# STM32F1_Rev0_2.net
KiCad netlist of a schematic drawn in EAGLE
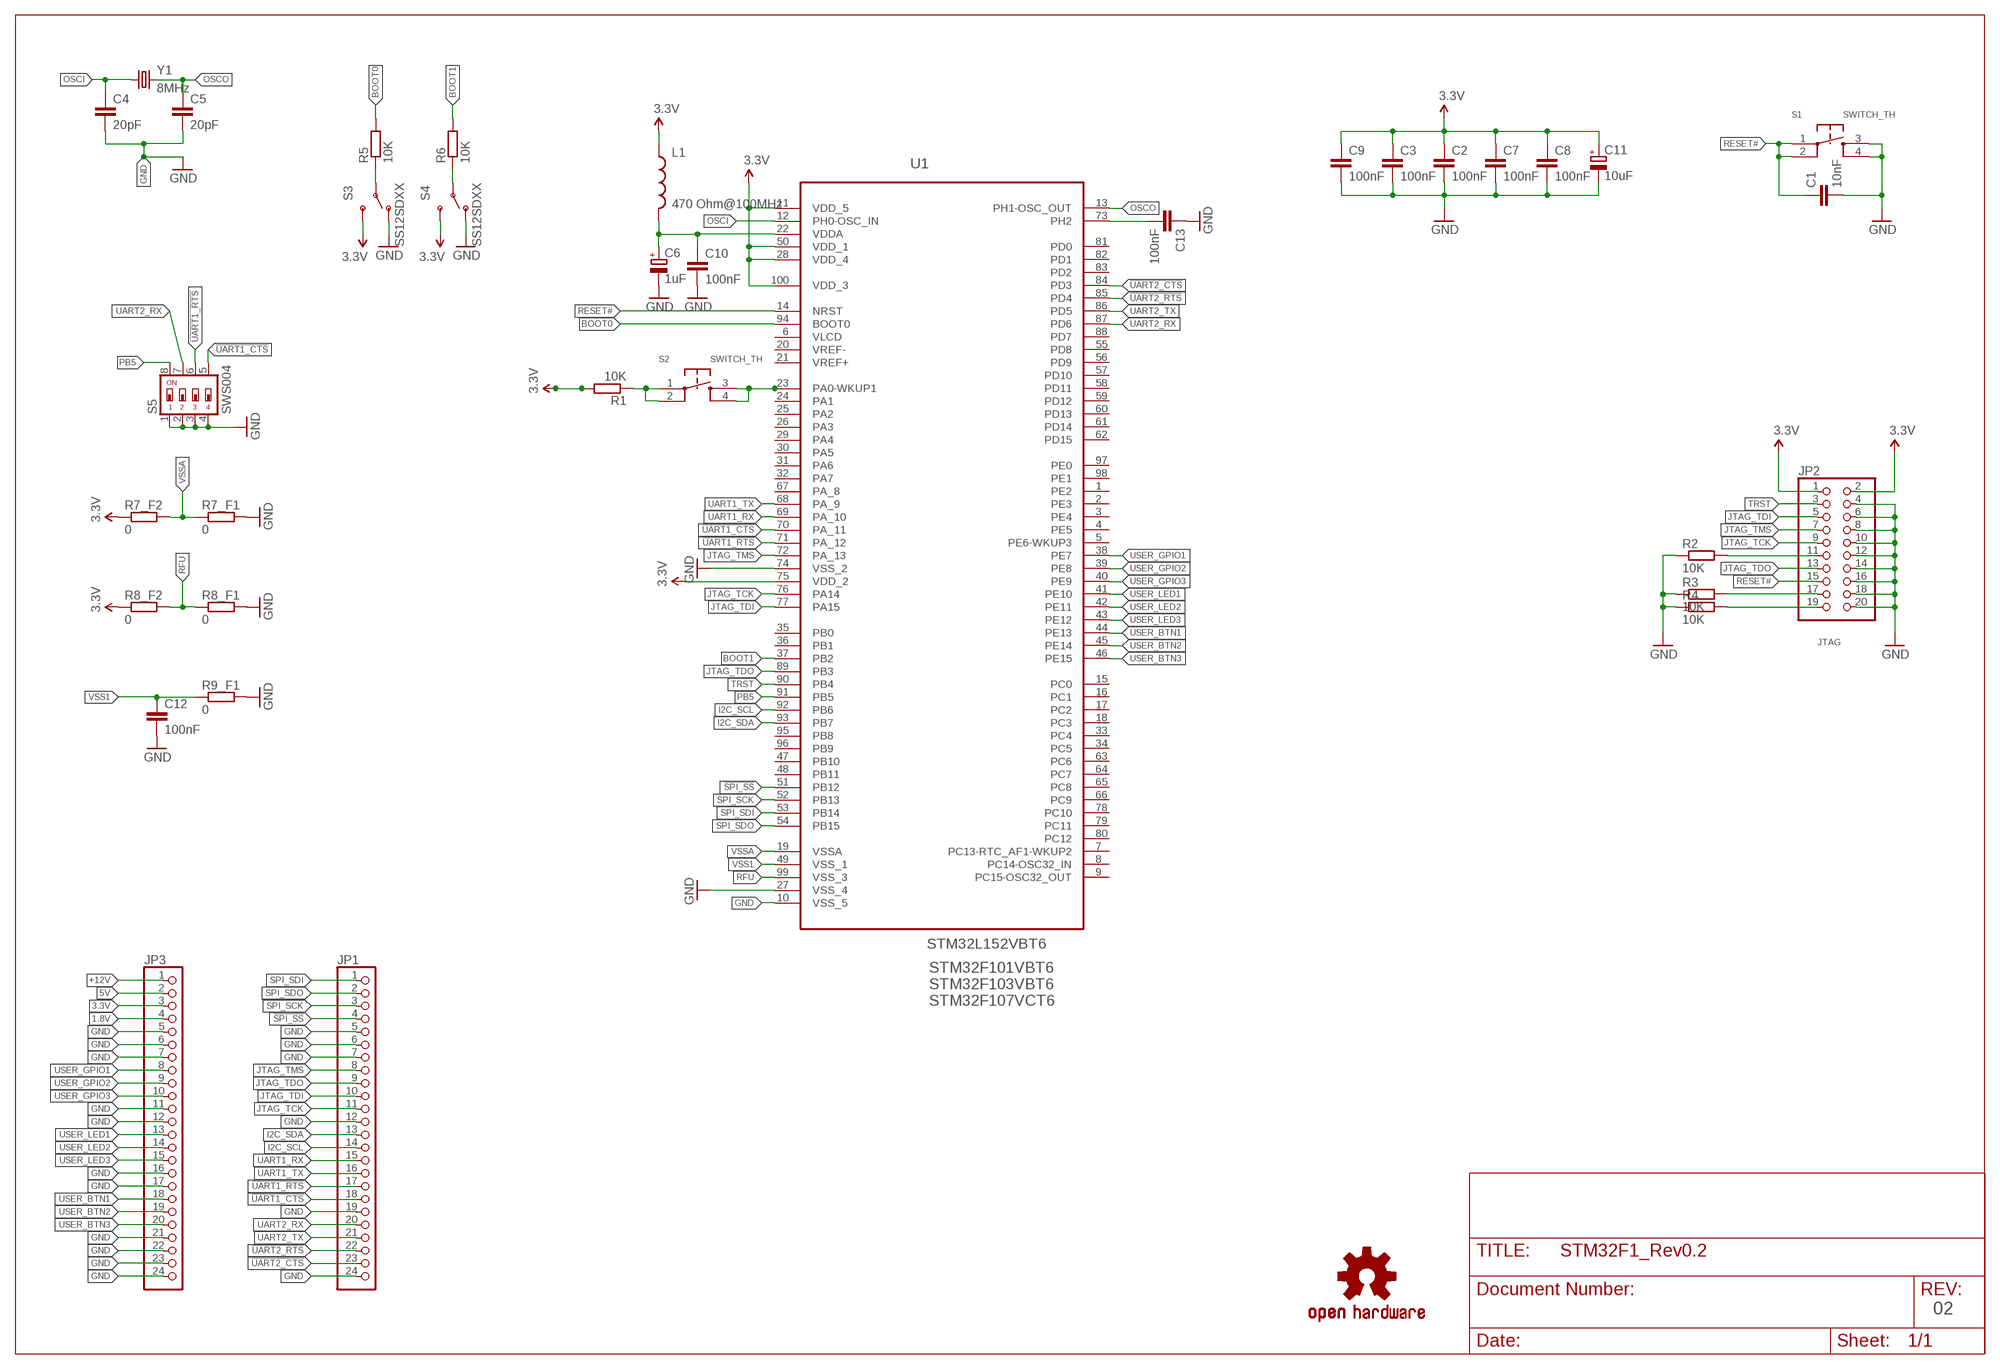
[diagram p0: schematic, sheet 1]

(export (version "E")
  (design (tool "Eeschema 10.0.6"))
  (components
    (comp (ref "C1")
      (value "10nF")
      (footprint "eagle-import:C0805K")
      (libsource (lib "eagle-import") (part "C-EUC0805K"))
    )
    (comp (ref "C2")
      (value "100nF")
      (footprint "eagle-import:C0805K")
      (libsource (lib "eagle-import") (part "C-EUC0805K"))
    )
    (comp (ref "C3")
      (value "100nF")
      (footprint "eagle-import:C0805K")
      (libsource (lib "eagle-import") (part "C-EUC0805K"))
    )
    (comp (ref "C4")
      (value "20pF")
      (footprint "eagle-import:C0805K")
      (libsource (lib "eagle-import") (part "C-EUC0805K"))
    )
    (comp (ref "C5")
      (value "20pF")
      (footprint "eagle-import:C0805K")
      (libsource (lib "eagle-import") (part "C-EUC0805K"))
    )
    (comp (ref "C6")
      (value "1uF")
      (footprint "eagle-import:PANASONIC_B")
      (libsource (lib "eagle-import") (part "CPOL-EUB"))
    )
    (comp (ref "C7")
      (value "100nF")
      (footprint "eagle-import:C0805K")
      (libsource (lib "eagle-import") (part "C-EUC0805K"))
    )
    (comp (ref "C8")
      (value "100nF")
      (footprint "eagle-import:C0805K")
      (libsource (lib "eagle-import") (part "C-EUC0805K"))
    )
    (comp (ref "C9")
      (value "100nF")
      (footprint "eagle-import:C0805K")
      (libsource (lib "eagle-import") (part "C-EUC0805K"))
    )
    (comp (ref "C10")
      (value "100nF")
      (footprint "eagle-import:C0805K")
      (libsource (lib "eagle-import") (part "C-EUC0805K"))
    )
    (comp (ref "C11")
      (value "10uF")
      (footprint "eagle-import:PANASONIC_B")
      (libsource (lib "eagle-import") (part "CPOL-EUB"))
    )
    (comp (ref "C12")
      (value "100nF")
      (footprint "eagle-import:C0805K")
      (libsource (lib "eagle-import") (part "C-EUC0805K"))
    )
    (comp (ref "C13")
      (value "100nF")
      (footprint "eagle-import:C0805K")
      (libsource (lib "eagle-import") (part "C-EUC0805K"))
    )
    (comp (ref "JP1")
      (value "PINHD-1X24")
      (footprint "eagle-import:1X24")
      (libsource (lib "eagle-import") (part "PINHD-1X24"))
    )
    (comp (ref "JP2")
      (value "PINHD-2X10")
      (footprint "eagle-import:2X10")
      (libsource (lib "eagle-import") (part "PINHD-2X10"))
    )
    (comp (ref "JP3")
      (value "PINHD-1X24")
      (footprint "eagle-import:1X24")
      (libsource (lib "eagle-import") (part "PINHD-1X24"))
    )
    (comp (ref "L1")
      (value "470 Ohm@100MHz")
      (footprint "eagle-import:0805")
      (libsource (lib "eagle-import") (part "INDUCTOR0805"))
    )
    (comp (ref "R1")
      (value "10K")
      (footprint "eagle-import:R0805")
      (libsource (lib "eagle-import") (part "R-EU_R0805"))
    )
    (comp (ref "R2")
      (value "10K")
      (footprint "eagle-import:R0805")
      (libsource (lib "eagle-import") (part "R-EU_R0805"))
    )
    (comp (ref "R3")
      (value "10K")
      (footprint "eagle-import:R0805")
      (libsource (lib "eagle-import") (part "R-EU_R0805"))
    )
    (comp (ref "R4")
      (value "10K")
      (footprint "eagle-import:R0805")
      (libsource (lib "eagle-import") (part "R-EU_R0805"))
    )
    (comp (ref "R5")
      (value "10K")
      (footprint "eagle-import:R0805")
      (libsource (lib "eagle-import") (part "R-EU_R0805"))
    )
    (comp (ref "R6")
      (value "10K")
      (footprint "eagle-import:R0805")
      (libsource (lib "eagle-import") (part "R-EU_R0805"))
    )
    (comp (ref "R7_F1")
      (value "0")
      (footprint "eagle-import:R0805")
      (libsource (lib "eagle-import") (part "R-EU_R0805"))
    )
    (comp (ref "R7_F2")
      (value "0")
      (footprint "eagle-import:R0805")
      (libsource (lib "eagle-import") (part "R-EU_R0805"))
    )
    (comp (ref "R8_F1")
      (value "0")
      (footprint "eagle-import:R0805")
      (libsource (lib "eagle-import") (part "R-EU_R0805"))
    )
    (comp (ref "R8_F2")
      (value "0")
      (footprint "eagle-import:R0805")
      (libsource (lib "eagle-import") (part "R-EU_R0805"))
    )
    (comp (ref "R9_F1")
      (value "0")
      (footprint "eagle-import:R0805")
      (libsource (lib "eagle-import") (part "R-EU_R0805"))
    )
    (comp (ref "S1")
      (value "SWITCH_TH")
      (footprint "eagle-import:SWITCH_TROUGHHOLE")
      (libsource (lib "eagle-import") (part "SWITCH_TH"))
    )
    (comp (ref "S2")
      (value "SWITCH_TH")
      (footprint "eagle-import:SWITCH_TROUGHHOLE")
      (libsource (lib "eagle-import") (part "SWITCH_TH"))
    )
    (comp (ref "S3")
      (value "SS12SDXX")
      (footprint "eagle-import:SS12SDXX")
      (libsource (lib "eagle-import") (part "SS12SDXX"))
    )
    (comp (ref "S4")
      (value "SS12SDXX")
      (footprint "eagle-import:SS12SDXX")
      (libsource (lib "eagle-import") (part "SS12SDXX"))
    )
    (comp (ref "S5")
      (value "SWS004")
      (footprint "eagle-import:SMS-004")
      (libsource (lib "eagle-import") (part "SWS004"))
    )
    (comp (ref "U$1")
      (value "OSHW-LOGOS")
      (footprint "eagle-import:OSHW-LOGO-S")
      (libsource (lib "eagle-import") (part "OSHW-LOGOS"))
    )
    (comp (ref "U1")
      (value "STM32L152VBT6")
      (footprint "eagle-import:QFP50P1600X1600X160-100N")
      (libsource (lib "eagle-import") (part "STM32L152VBT6"))
    )
    (comp (ref "Y1")
      (value "8MHz")
      (footprint "eagle-import:HC49UP")
      (libsource (lib "eagle-import") (part "CRYSTALSMD"))
    )
  )
  (nets
    (net (code "1") (name "+12V") (class "Default")
      (node (ref "JP3") (pin "1") (pinfunction "1_1") (pintype "passive"))
    )
    (net (code "2") (name "/VLCD") (class "Default")
      (node (ref "U1") (pin "6") (pinfunction "VLCD_6") (pintype "power_in"))
    )
    (net (code "3") (name "/~{SPI_SS}") (class "Default")
      (node (ref "JP1") (pin "4") (pinfunction "4_4") (pintype "passive"))
      (node (ref "U1") (pin "51") (pinfunction "PB12_51") (pintype "bidirectional"))
    )
    (net (code "4") (name "/~{UART1_CTS}") (class "Default")
      (node (ref "JP1") (pin "18") (pinfunction "18_18") (pintype "passive"))
      (node (ref "S5") (pin "5") (pinfunction "5_5") (pintype "passive"))
      (node (ref "U1") (pin "70") (pinfunction "PA_11_70") (pintype "bidirectional"))
    )
    (net (code "5") (name "/~{UART1_RTS}") (class "Default")
      (node (ref "JP1") (pin "17") (pinfunction "17_17") (pintype "passive"))
      (node (ref "S5") (pin "6") (pinfunction "6_6") (pintype "passive"))
      (node (ref "U1") (pin "71") (pinfunction "PA_12_71") (pintype "bidirectional"))
    )
    (net (code "6") (name "/~{UART2_CTS}") (class "Default")
      (node (ref "JP1") (pin "23") (pinfunction "23_23") (pintype "passive"))
      (node (ref "U1") (pin "84") (pinfunction "PD3_84") (pintype "bidirectional"))
    )
    (net (code "7") (name "/~{UART2_RTS}") (class "Default")
      (node (ref "JP1") (pin "22") (pinfunction "22_22") (pintype "passive"))
      (node (ref "U1") (pin "85") (pinfunction "PD4_85") (pintype "bidirectional"))
    )
    (net (code "8") (name "1.8V") (class "Default")
      (node (ref "JP3") (pin "4") (pinfunction "4_4") (pintype "passive"))
    )
    (net (code "9") (name "3.3V") (class "Default")
      (node (ref "C11") (pin "+") (pinfunction "+_+") (pintype "passive"))
      (node (ref "C2") (pin "1") (pinfunction "1_1") (pintype "passive"))
      (node (ref "C3") (pin "1") (pinfunction "1_1") (pintype "passive"))
      (node (ref "C7") (pin "1") (pinfunction "1_1") (pintype "passive"))
      (node (ref "C8") (pin "1") (pinfunction "1_1") (pintype "passive"))
      (node (ref "C9") (pin "1") (pinfunction "1_1") (pintype "passive"))
      (node (ref "JP2") (pin "1") (pinfunction "1_1") (pintype "passive"))
      (node (ref "JP2") (pin "2") (pinfunction "2_2") (pintype "passive"))
      (node (ref "JP3") (pin "3") (pinfunction "3_3") (pintype "passive"))
      (node (ref "L1") (pin "1") (pinfunction "1_1") (pintype "passive"))
      (node (ref "R1") (pin "2") (pinfunction "2_2") (pintype "passive"))
      (node (ref "R7_F2") (pin "1") (pinfunction "1_1") (pintype "passive"))
      (node (ref "R8_F2") (pin "1") (pinfunction "1_1") (pintype "passive"))
      (node (ref "S3") (pin "3") (pinfunction "3_3") (pintype "passive"))
      (node (ref "S4") (pin "3") (pinfunction "3_3") (pintype "passive"))
      (node (ref "U1") (pin "100") (pinfunction "VDD_3_100") (pintype "power_in"))
      (node (ref "U1") (pin "11") (pinfunction "VDD_5_11") (pintype "power_in"))
      (node (ref "U1") (pin "28") (pinfunction "VDD_4_28") (pintype "power_in"))
      (node (ref "U1") (pin "50") (pinfunction "VDD_1_50") (pintype "power_in"))
      (node (ref "U1") (pin "75") (pinfunction "VDD_2_75") (pintype "power_in"))
    )
    (net (code "10") (name "5V") (class "Default")
      (node (ref "JP3") (pin "2") (pinfunction "2_2") (pintype "passive"))
    )
    (net (code "11") (name "BOOT0") (class "Default")
      (node (ref "R5") (pin "2") (pinfunction "2_2") (pintype "passive"))
      (node (ref "U1") (pin "94") (pinfunction "BOOT0_94") (pintype "input"))
    )
    (net (code "12") (name "BOOT1") (class "Default")
      (node (ref "R6") (pin "2") (pinfunction "2_2") (pintype "passive"))
      (node (ref "U1") (pin "37") (pinfunction "PB2_37") (pintype "bidirectional"))
    )
    (net (code "13") (name "GND") (class "Default")
      (node (ref "C1") (pin "2") (pinfunction "2_2") (pintype "passive"))
      (node (ref "C10") (pin "2") (pinfunction "2_2") (pintype "passive"))
      (node (ref "C11") (pin "-") (pinfunction "-_-") (pintype "passive"))
      (node (ref "C12") (pin "2") (pinfunction "2_2") (pintype "passive"))
      (node (ref "C13") (pin "1") (pinfunction "1_1") (pintype "passive"))
      (node (ref "C2") (pin "2") (pinfunction "2_2") (pintype "passive"))
      (node (ref "C3") (pin "2") (pinfunction "2_2") (pintype "passive"))
      (node (ref "C4") (pin "2") (pinfunction "2_2") (pintype "passive"))
      (node (ref "C5") (pin "2") (pinfunction "2_2") (pintype "passive"))
      (node (ref "C6") (pin "-") (pinfunction "-_-") (pintype "passive"))
      (node (ref "C7") (pin "2") (pinfunction "2_2") (pintype "passive"))
      (node (ref "C8") (pin "2") (pinfunction "2_2") (pintype "passive"))
      (node (ref "C9") (pin "2") (pinfunction "2_2") (pintype "passive"))
      (node (ref "JP1") (pin "12") (pinfunction "12_12") (pintype "passive"))
      (node (ref "JP1") (pin "19") (pinfunction "19_19") (pintype "passive"))
      (node (ref "JP1") (pin "24") (pinfunction "24_24") (pintype "passive"))
      (node (ref "JP1") (pin "5") (pinfunction "5_5") (pintype "passive"))
      (node (ref "JP1") (pin "6") (pinfunction "6_6") (pintype "passive"))
      (node (ref "JP1") (pin "7") (pinfunction "7_7") (pintype "passive"))
      (node (ref "JP2") (pin "10") (pinfunction "10_10") (pintype "passive"))
      (node (ref "JP2") (pin "12") (pinfunction "12_12") (pintype "passive"))
      (node (ref "JP2") (pin "14") (pinfunction "14_14") (pintype "passive"))
      (node (ref "JP2") (pin "16") (pinfunction "16_16") (pintype "passive"))
      (node (ref "JP2") (pin "18") (pinfunction "18_18") (pintype "passive"))
      (node (ref "JP2") (pin "20") (pinfunction "20_20") (pintype "passive"))
      (node (ref "JP2") (pin "4") (pinfunction "4_4") (pintype "passive"))
      (node (ref "JP2") (pin "6") (pinfunction "6_6") (pintype "passive"))
      (node (ref "JP2") (pin "8") (pinfunction "8_8") (pintype "passive"))
      (node (ref "JP3") (pin "11") (pinfunction "11_11") (pintype "passive"))
      (node (ref "JP3") (pin "12") (pinfunction "12_12") (pintype "passive"))
      (node (ref "JP3") (pin "16") (pinfunction "16_16") (pintype "passive"))
      (node (ref "JP3") (pin "17") (pinfunction "17_17") (pintype "passive"))
      (node (ref "JP3") (pin "21") (pinfunction "21_21") (pintype "passive"))
      (node (ref "JP3") (pin "22") (pinfunction "22_22") (pintype "passive"))
      (node (ref "JP3") (pin "23") (pinfunction "23_23") (pintype "passive"))
      (node (ref "JP3") (pin "24") (pinfunction "24_24") (pintype "passive"))
      (node (ref "JP3") (pin "5") (pinfunction "5_5") (pintype "passive"))
      (node (ref "JP3") (pin "6") (pinfunction "6_6") (pintype "passive"))
      (node (ref "JP3") (pin "7") (pinfunction "7_7") (pintype "passive"))
      (node (ref "R2") (pin "1") (pinfunction "1_1") (pintype "passive"))
      (node (ref "R3") (pin "1") (pinfunction "1_1") (pintype "passive"))
      (node (ref "R4") (pin "1") (pinfunction "1_1") (pintype "passive"))
      (node (ref "R7_F1") (pin "2") (pinfunction "2_2") (pintype "passive"))
      (node (ref "R8_F1") (pin "2") (pinfunction "2_2") (pintype "passive"))
      (node (ref "R9_F1") (pin "2") (pinfunction "2_2") (pintype "passive"))
      (node (ref "S1") (pin "3") (pintype "bidirectional"))
      (node (ref "S1") (pin "4") (pintype "bidirectional"))
      (node (ref "S3") (pin "1") (pinfunction "1_1") (pintype "passive"))
      (node (ref "S4") (pin "1") (pinfunction "1_1") (pintype "passive"))
      (node (ref "S5") (pin "1") (pinfunction "1_1") (pintype "passive"))
      (node (ref "S5") (pin "2") (pinfunction "2_2") (pintype "passive"))
      (node (ref "S5") (pin "3") (pinfunction "3_3") (pintype "passive"))
      (node (ref "S5") (pin "4") (pinfunction "4_4") (pintype "passive"))
      (node (ref "U1") (pin "10") (pinfunction "VSS_5_10") (pintype "power_in"))
      (node (ref "U1") (pin "27") (pinfunction "VSS_4_27") (pintype "power_in"))
      (node (ref "U1") (pin "74") (pinfunction "VSS_2_74") (pintype "power_in"))
    )
    (net (code "14") (name "I2C_SCL") (class "Default")
      (node (ref "JP1") (pin "14") (pinfunction "14_14") (pintype "passive"))
      (node (ref "U1") (pin "92") (pinfunction "PB6_92") (pintype "bidirectional"))
    )
    (net (code "15") (name "I2C_SDA") (class "Default")
      (node (ref "JP1") (pin "13") (pinfunction "13_13") (pintype "passive"))
      (node (ref "U1") (pin "93") (pinfunction "PB7_93") (pintype "bidirectional"))
    )
    (net (code "16") (name "JTAG_TCK") (class "Default")
      (node (ref "JP1") (pin "11") (pinfunction "11_11") (pintype "passive"))
      (node (ref "JP2") (pin "9") (pinfunction "9_9") (pintype "passive"))
      (node (ref "U1") (pin "76") (pinfunction "PA14_76") (pintype "bidirectional"))
    )
    (net (code "17") (name "JTAG_TDI") (class "Default")
      (node (ref "JP1") (pin "10") (pinfunction "10_10") (pintype "passive"))
      (node (ref "JP2") (pin "5") (pinfunction "5_5") (pintype "passive"))
      (node (ref "U1") (pin "77") (pinfunction "PA15_77") (pintype "bidirectional"))
    )
    (net (code "18") (name "JTAG_TDO") (class "Default")
      (node (ref "JP1") (pin "9") (pinfunction "9_9") (pintype "passive"))
      (node (ref "JP2") (pin "13") (pinfunction "13_13") (pintype "passive"))
      (node (ref "U1") (pin "89") (pinfunction "PB3_89") (pintype "bidirectional"))
    )
    (net (code "19") (name "JTAG_TMS") (class "Default")
      (node (ref "JP1") (pin "8") (pinfunction "8_8") (pintype "passive"))
      (node (ref "JP2") (pin "7") (pinfunction "7_7") (pintype "passive"))
      (node (ref "U1") (pin "72") (pinfunction "PA_13_72") (pintype "bidirectional"))
    )
    (net (code "20") (name "Net-(JP2-Pad11)") (class "Default")
      (node (ref "JP2") (pin "11") (pinfunction "11_11") (pintype "passive"))
      (node (ref "R2") (pin "2") (pinfunction "2_2") (pintype "passive"))
    )
    (net (code "21") (name "Net-(JP2-Pad17)") (class "Default")
      (node (ref "JP2") (pin "17") (pinfunction "17_17") (pintype "passive"))
      (node (ref "R3") (pin "2") (pinfunction "2_2") (pintype "passive"))
    )
    (net (code "22") (name "Net-(JP2-Pad19)") (class "Default")
      (node (ref "JP2") (pin "19") (pinfunction "19_19") (pintype "passive"))
      (node (ref "R4") (pin "2") (pinfunction "2_2") (pintype "passive"))
    )
    (net (code "23") (name "Net-(R1-Pad1)") (class "Default")
      (node (ref "R1") (pin "1") (pinfunction "1_1") (pintype "passive"))
      (node (ref "S2") (pin "1") (pintype "bidirectional"))
      (node (ref "S2") (pin "2") (pintype "bidirectional"))
    )
    (net (code "24") (name "Net-(R5-Pad1)") (class "Default")
      (node (ref "R5") (pin "1") (pinfunction "1_1") (pintype "passive"))
      (node (ref "S3") (pin "2") (pinfunction "2_2") (pintype "passive"))
    )
    (net (code "25") (name "Net-(R6-Pad1)") (class "Default")
      (node (ref "R6") (pin "1") (pinfunction "1_1") (pintype "passive"))
      (node (ref "S4") (pin "2") (pinfunction "2_2") (pintype "passive"))
    )
    (net (code "26") (name "Net-(U1-PA0-WKUP1)") (class "Default")
      (node (ref "S2") (pin "3") (pintype "bidirectional"))
      (node (ref "S2") (pin "4") (pintype "bidirectional"))
      (node (ref "U1") (pin "23") (pinfunction "PA0-WKUP1_23") (pintype "bidirectional"))
    )
    (net (code "27") (name "Net-(U1-PH2)") (class "Default")
      (node (ref "C13") (pin "2") (pinfunction "2_2") (pintype "passive"))
      (node (ref "U1") (pin "73") (pinfunction "PH2_73") (pintype "bidirectional"))
    )
    (net (code "28") (name "Net-(U1-VDDA)") (class "Default")
      (node (ref "C10") (pin "1") (pinfunction "1_1") (pintype "passive"))
      (node (ref "C6") (pin "+") (pinfunction "+_+") (pintype "passive"))
      (node (ref "L1") (pin "2") (pinfunction "2_2") (pintype "passive"))
      (node (ref "U1") (pin "22") (pinfunction "VDDA_22") (pintype "power_in"))
    )
    (net (code "29") (name "OSCI") (class "Default")
      (node (ref "C4") (pin "1") (pinfunction "1_1") (pintype "passive"))
      (node (ref "U1") (pin "12") (pinfunction "PH0-OSC_IN_12") (pintype "input"))
      (node (ref "Y1") (pin "1") (pinfunction "1_1") (pintype "passive"))
    )
    (net (code "30") (name "OSCO") (class "Default")
      (node (ref "C5") (pin "1") (pinfunction "1_1") (pintype "passive"))
      (node (ref "U1") (pin "13") (pinfunction "PH1-OSC_OUT_13") (pintype "output"))
      (node (ref "Y1") (pin "2") (pinfunction "2_2") (pintype "passive"))
    )
    (net (code "31") (name "PB5") (class "Default")
      (node (ref "S5") (pin "8") (pinfunction "8_8") (pintype "passive"))
      (node (ref "U1") (pin "91") (pinfunction "PB5_91") (pintype "bidirectional"))
    )
    (net (code "32") (name "RESET#") (class "Default")
      (node (ref "C1") (pin "1") (pinfunction "1_1") (pintype "passive"))
      (node (ref "JP2") (pin "15") (pinfunction "15_15") (pintype "passive"))
      (node (ref "S1") (pin "1") (pintype "bidirectional"))
      (node (ref "S1") (pin "2") (pintype "bidirectional"))
      (node (ref "U1") (pin "14") (pinfunction "NRST_14") (pintype "bidirectional"))
    )
    (net (code "33") (name "RFU") (class "Default")
      (node (ref "R8_F1") (pin "1") (pinfunction "1_1") (pintype "passive"))
      (node (ref "R8_F2") (pin "2") (pinfunction "2_2") (pintype "passive"))
      (node (ref "U1") (pin "99") (pinfunction "VSS_3_99") (pintype "power_in"))
    )
    (net (code "34") (name "SPI_SCK") (class "Default")
      (node (ref "JP1") (pin "3") (pinfunction "3_3") (pintype "passive"))
      (node (ref "U1") (pin "52") (pinfunction "PB13_52") (pintype "bidirectional"))
    )
    (net (code "35") (name "SPI_SDI") (class "Default")
      (node (ref "JP1") (pin "1") (pinfunction "1_1") (pintype "passive"))
      (node (ref "U1") (pin "53") (pinfunction "PB14_53") (pintype "bidirectional"))
    )
    (net (code "36") (name "SPI_SDO") (class "Default")
      (node (ref "JP1") (pin "2") (pinfunction "2_2") (pintype "passive"))
      (node (ref "U1") (pin "54") (pinfunction "PB15_54") (pintype "bidirectional"))
    )
    (net (code "37") (name "TRST") (class "Default")
      (node (ref "JP2") (pin "3") (pinfunction "3_3") (pintype "passive"))
      (node (ref "U1") (pin "90") (pinfunction "PB4_90") (pintype "bidirectional"))
    )
    (net (code "38") (name "UART1_RX") (class "Default")
      (node (ref "JP1") (pin "15") (pinfunction "15_15") (pintype "passive"))
      (node (ref "U1") (pin "69") (pinfunction "PA_10_69") (pintype "bidirectional"))
    )
    (net (code "39") (name "UART1_TX") (class "Default")
      (node (ref "JP1") (pin "16") (pinfunction "16_16") (pintype "passive"))
      (node (ref "U1") (pin "68") (pinfunction "PA_9_68") (pintype "bidirectional"))
    )
    (net (code "40") (name "UART2_RX") (class "Default")
      (node (ref "JP1") (pin "20") (pinfunction "20_20") (pintype "passive"))
      (node (ref "S5") (pin "7") (pinfunction "7_7") (pintype "passive"))
      (node (ref "U1") (pin "87") (pinfunction "PD6_87") (pintype "bidirectional"))
    )
    (net (code "41") (name "UART2_TX") (class "Default")
      (node (ref "JP1") (pin "21") (pinfunction "21_21") (pintype "passive"))
      (node (ref "U1") (pin "86") (pinfunction "PD5_86") (pintype "bidirectional"))
    )
    (net (code "42") (name "USER_BTN1") (class "Default")
      (node (ref "JP3") (pin "18") (pinfunction "18_18") (pintype "passive"))
      (node (ref "U1") (pin "44") (pinfunction "PE13_44") (pintype "bidirectional"))
    )
    (net (code "43") (name "USER_BTN2") (class "Default")
      (node (ref "JP3") (pin "19") (pinfunction "19_19") (pintype "passive"))
      (node (ref "U1") (pin "45") (pinfunction "PE14_45") (pintype "bidirectional"))
    )
    (net (code "44") (name "USER_BTN3") (class "Default")
      (node (ref "JP3") (pin "20") (pinfunction "20_20") (pintype "passive"))
      (node (ref "U1") (pin "46") (pinfunction "PE15_46") (pintype "bidirectional"))
    )
    (net (code "45") (name "USER_GPIO1") (class "Default")
      (node (ref "JP3") (pin "8") (pinfunction "8_8") (pintype "passive"))
      (node (ref "U1") (pin "38") (pinfunction "PE7_38") (pintype "bidirectional"))
    )
    (net (code "46") (name "USER_GPIO2") (class "Default")
      (node (ref "JP3") (pin "9") (pinfunction "9_9") (pintype "passive"))
      (node (ref "U1") (pin "39") (pinfunction "PE8_39") (pintype "bidirectional"))
    )
    (net (code "47") (name "USER_GPIO3") (class "Default")
      (node (ref "JP3") (pin "10") (pinfunction "10_10") (pintype "passive"))
      (node (ref "U1") (pin "40") (pinfunction "PE9_40") (pintype "bidirectional"))
    )
    (net (code "48") (name "USER_LED1") (class "Default")
      (node (ref "JP3") (pin "13") (pinfunction "13_13") (pintype "passive"))
      (node (ref "U1") (pin "41") (pinfunction "PE10_41") (pintype "bidirectional"))
    )
    (net (code "49") (name "USER_LED2") (class "Default")
      (node (ref "JP3") (pin "14") (pinfunction "14_14") (pintype "passive"))
      (node (ref "U1") (pin "42") (pinfunction "PE11_42") (pintype "bidirectional"))
    )
    (net (code "50") (name "USER_LED3") (class "Default")
      (node (ref "JP3") (pin "15") (pinfunction "15_15") (pintype "passive"))
      (node (ref "U1") (pin "43") (pinfunction "PE12_43") (pintype "bidirectional"))
    )
    (net (code "51") (name "VSS1") (class "Default")
      (node (ref "C12") (pin "1") (pinfunction "1_1") (pintype "passive"))
      (node (ref "R9_F1") (pin "1") (pinfunction "1_1") (pintype "passive"))
      (node (ref "U1") (pin "49") (pinfunction "VSS_1_49") (pintype "power_in"))
    )
    (net (code "52") (name "VSSA") (class "Default")
      (node (ref "R7_F1") (pin "1") (pinfunction "1_1") (pintype "passive"))
      (node (ref "R7_F2") (pin "2") (pinfunction "2_2") (pintype "passive"))
      (node (ref "U1") (pin "19") (pinfunction "VSSA_19") (pintype "power_in"))
    )
    (net (code "53") (name "unconnected-(U1-PA1-Pad24)") (class "Default")
      (node (ref "U1") (pin "24") (pinfunction "PA1_24") (pintype "bidirectional"))
    )
    (net (code "54") (name "unconnected-(U1-PA2-Pad25)") (class "Default")
      (node (ref "U1") (pin "25") (pinfunction "PA2_25") (pintype "bidirectional"))
    )
    (net (code "55") (name "unconnected-(U1-PA3-Pad26)") (class "Default")
      (node (ref "U1") (pin "26") (pinfunction "PA3_26") (pintype "bidirectional"))
    )
    (net (code "56") (name "unconnected-(U1-PA4-Pad29)") (class "Default")
      (node (ref "U1") (pin "29") (pinfunction "PA4_29") (pintype "bidirectional"))
    )
    (net (code "57") (name "unconnected-(U1-PA5-Pad30)") (class "Default")
      (node (ref "U1") (pin "30") (pinfunction "PA5_30") (pintype "bidirectional"))
    )
    (net (code "58") (name "unconnected-(U1-PA6-Pad31)") (class "Default")
      (node (ref "U1") (pin "31") (pinfunction "PA6_31") (pintype "bidirectional"))
    )
    (net (code "59") (name "unconnected-(U1-PA7-Pad32)") (class "Default")
      (node (ref "U1") (pin "32") (pinfunction "PA7_32") (pintype "bidirectional"))
    )
    (net (code "60") (name "unconnected-(U1-PA_8-Pad67)") (class "Default")
      (node (ref "U1") (pin "67") (pinfunction "PA_8_67") (pintype "bidirectional"))
    )
    (net (code "61") (name "unconnected-(U1-PB0-Pad35)") (class "Default")
      (node (ref "U1") (pin "35") (pinfunction "PB0_35") (pintype "bidirectional"))
    )
    (net (code "62") (name "unconnected-(U1-PB1-Pad36)") (class "Default")
      (node (ref "U1") (pin "36") (pinfunction "PB1_36") (pintype "bidirectional"))
    )
    (net (code "63") (name "unconnected-(U1-PB8-Pad95)") (class "Default")
      (node (ref "U1") (pin "95") (pinfunction "PB8_95") (pintype "bidirectional"))
    )
    (net (code "64") (name "unconnected-(U1-PB9-Pad96)") (class "Default")
      (node (ref "U1") (pin "96") (pinfunction "PB9_96") (pintype "bidirectional"))
    )
    (net (code "65") (name "unconnected-(U1-PB10-Pad47)") (class "Default")
      (node (ref "U1") (pin "47") (pinfunction "PB10_47") (pintype "bidirectional"))
    )
    (net (code "66") (name "unconnected-(U1-PB11-Pad48)") (class "Default")
      (node (ref "U1") (pin "48") (pinfunction "PB11_48") (pintype "bidirectional"))
    )
    (net (code "67") (name "unconnected-(U1-PC0-Pad15)") (class "Default")
      (node (ref "U1") (pin "15") (pinfunction "PC0_15") (pintype "bidirectional"))
    )
    (net (code "68") (name "unconnected-(U1-PC1-Pad16)") (class "Default")
      (node (ref "U1") (pin "16") (pinfunction "PC1_16") (pintype "bidirectional"))
    )
    (net (code "69") (name "unconnected-(U1-PC2-Pad17)") (class "Default")
      (node (ref "U1") (pin "17") (pinfunction "PC2_17") (pintype "bidirectional"))
    )
    (net (code "70") (name "unconnected-(U1-PC3-Pad18)") (class "Default")
      (node (ref "U1") (pin "18") (pinfunction "PC3_18") (pintype "bidirectional"))
    )
    (net (code "71") (name "unconnected-(U1-PC4-Pad33)") (class "Default")
      (node (ref "U1") (pin "33") (pinfunction "PC4_33") (pintype "bidirectional"))
    )
    (net (code "72") (name "unconnected-(U1-PC5-Pad34)") (class "Default")
      (node (ref "U1") (pin "34") (pinfunction "PC5_34") (pintype "bidirectional"))
    )
    (net (code "73") (name "unconnected-(U1-PC6-Pad63)") (class "Default")
      (node (ref "U1") (pin "63") (pinfunction "PC6_63") (pintype "bidirectional"))
    )
    (net (code "74") (name "unconnected-(U1-PC7-Pad64)") (class "Default")
      (node (ref "U1") (pin "64") (pinfunction "PC7_64") (pintype "bidirectional"))
    )
    (net (code "75") (name "unconnected-(U1-PC8-Pad65)") (class "Default")
      (node (ref "U1") (pin "65") (pinfunction "PC8_65") (pintype "bidirectional"))
    )
    (net (code "76") (name "unconnected-(U1-PC9-Pad66)") (class "Default")
      (node (ref "U1") (pin "66") (pinfunction "PC9_66") (pintype "bidirectional"))
    )
    (net (code "77") (name "unconnected-(U1-PC10-Pad78)") (class "Default")
      (node (ref "U1") (pin "78") (pinfunction "PC10_78") (pintype "bidirectional"))
    )
    (net (code "78") (name "unconnected-(U1-PC11-Pad79)") (class "Default")
      (node (ref "U1") (pin "79") (pinfunction "PC11_79") (pintype "bidirectional"))
    )
    (net (code "79") (name "unconnected-(U1-PC12-Pad80)") (class "Default")
      (node (ref "U1") (pin "80") (pinfunction "PC12_80") (pintype "bidirectional"))
    )
    (net (code "80") (name "unconnected-(U1-PC13-RTC_AF1-WKUP2-Pad7)") (class "Default")
      (node (ref "U1") (pin "7") (pinfunction "PC13-RTC_AF1-WKUP2_7") (pintype "bidirectional"))
    )
    (net (code "81") (name "unconnected-(U1-PC14-OSC32_IN-Pad8)") (class "Default")
      (node (ref "U1") (pin "8") (pinfunction "PC14-OSC32_IN_8") (pintype "bidirectional"))
    )
    (net (code "82") (name "unconnected-(U1-PC15-OSC32_OUT-Pad9)") (class "Default")
      (node (ref "U1") (pin "9") (pinfunction "PC15-OSC32_OUT_9") (pintype "bidirectional"))
    )
    (net (code "83") (name "unconnected-(U1-PD0-Pad81)") (class "Default")
      (node (ref "U1") (pin "81") (pinfunction "PD0_81") (pintype "bidirectional"))
    )
    (net (code "84") (name "unconnected-(U1-PD1-Pad82)") (class "Default")
      (node (ref "U1") (pin "82") (pinfunction "PD1_82") (pintype "bidirectional"))
    )
    (net (code "85") (name "unconnected-(U1-PD2-Pad83)") (class "Default")
      (node (ref "U1") (pin "83") (pinfunction "PD2_83") (pintype "bidirectional"))
    )
    (net (code "86") (name "unconnected-(U1-PD7-Pad88)") (class "Default")
      (node (ref "U1") (pin "88") (pinfunction "PD7_88") (pintype "bidirectional"))
    )
    (net (code "87") (name "unconnected-(U1-PD8-Pad55)") (class "Default")
      (node (ref "U1") (pin "55") (pinfunction "PD8_55") (pintype "bidirectional"))
    )
    (net (code "88") (name "unconnected-(U1-PD9-Pad56)") (class "Default")
      (node (ref "U1") (pin "56") (pinfunction "PD9_56") (pintype "bidirectional"))
    )
    (net (code "89") (name "unconnected-(U1-PD10-Pad57)") (class "Default")
      (node (ref "U1") (pin "57") (pinfunction "PD10_57") (pintype "bidirectional"))
    )
    (net (code "90") (name "unconnected-(U1-PD11-Pad58)") (class "Default")
      (node (ref "U1") (pin "58") (pinfunction "PD11_58") (pintype "bidirectional"))
    )
    (net (code "91") (name "unconnected-(U1-PD12-Pad59)") (class "Default")
      (node (ref "U1") (pin "59") (pinfunction "PD12_59") (pintype "bidirectional"))
    )
    (net (code "92") (name "unconnected-(U1-PD13-Pad60)") (class "Default")
      (node (ref "U1") (pin "60") (pinfunction "PD13_60") (pintype "bidirectional"))
    )
    (net (code "93") (name "unconnected-(U1-PD14-Pad61)") (class "Default")
      (node (ref "U1") (pin "61") (pinfunction "PD14_61") (pintype "bidirectional"))
    )
    (net (code "94") (name "unconnected-(U1-PD15-Pad62)") (class "Default")
      (node (ref "U1") (pin "62") (pinfunction "PD15_62") (pintype "bidirectional"))
    )
    (net (code "95") (name "unconnected-(U1-PE0-Pad97)") (class "Default")
      (node (ref "U1") (pin "97") (pinfunction "PE0_97") (pintype "bidirectional"))
    )
    (net (code "96") (name "unconnected-(U1-PE1-Pad98)") (class "Default")
      (node (ref "U1") (pin "98") (pinfunction "PE1_98") (pintype "bidirectional"))
    )
    (net (code "97") (name "unconnected-(U1-PE2-Pad1)") (class "Default")
      (node (ref "U1") (pin "1") (pinfunction "PE2_1") (pintype "bidirectional"))
    )
    (net (code "98") (name "unconnected-(U1-PE3-Pad2)") (class "Default")
      (node (ref "U1") (pin "2") (pinfunction "PE3_2") (pintype "bidirectional"))
    )
    (net (code "99") (name "unconnected-(U1-PE4-Pad3)") (class "Default")
      (node (ref "U1") (pin "3") (pinfunction "PE4_3") (pintype "bidirectional"))
    )
    (net (code "100") (name "unconnected-(U1-PE5-Pad4)") (class "Default")
      (node (ref "U1") (pin "4") (pinfunction "PE5_4") (pintype "bidirectional"))
    )
    (net (code "101") (name "unconnected-(U1-PE6-WKUP3-Pad5)") (class "Default")
      (node (ref "U1") (pin "5") (pinfunction "PE6-WKUP3_5") (pintype "bidirectional"))
    )
    (net (code "102") (name "unconnected-(U1-VREF+-Pad21)") (class "Default")
      (node (ref "U1") (pin "21") (pinfunction "VREF+_21") (pintype "input"))
    )
    (net (code "103") (name "unconnected-(U1-VREF--Pad20)") (class "Default")
      (node (ref "U1") (pin "20") (pinfunction "VREF-_20") (pintype "input"))
    )
  )
)
